# pinout_v1.net
KiCad netlist of a schematic drawn in Altium Designer
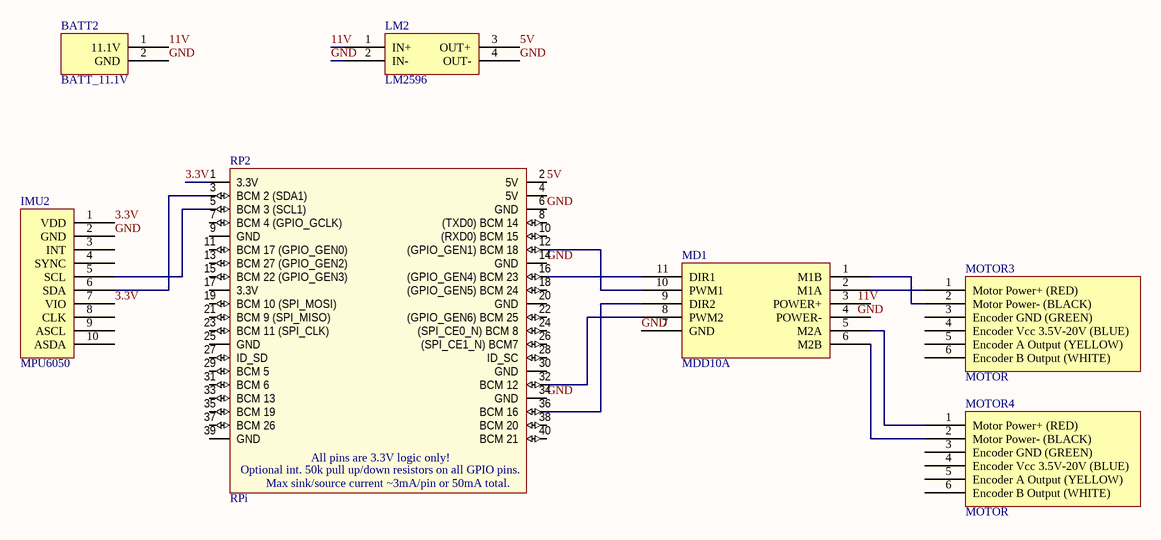
[diagram p0: pinout_v1.SchDoc]

(export (version "E")
  (design (tool "Eeschema 10.0.6"))
  (components
    (comp (ref "BATT2")
      (value "BATT_11.1V")
      (description "11.1V, 4000mAh, 40C 3S LiPo Battery")
      (libsource (lib "pinout") (part "BATT_11.1V"))
    )
    (comp (ref "IMU2")
      (value "MPU6050")
      (description "SparkFun Triple Axis Accelerometer and Gyro Breakout")
      (libsource (lib "pinout") (part "MPU6050"))
    )
    (comp (ref "LM2") (value "LM2596") (libsource (lib "pinout") (part "LM2596")))
    (comp (ref "MD1")
      (value "MDD10A")
      (description "Cytron 10A 5-30V Dual Channel DC Motor Driver")
      (libsource (lib "pinout") (part "MDD10A"))
    )
    (comp (ref "MOTOR3")
      (value "MOTOR")
      (description "30:1 Metal Gearmotor 37Dx68L mm with 64 CPR Encoder")
      (libsource (lib "pinout") (part "MOTOR"))
    )
    (comp (ref "MOTOR4")
      (value "MOTOR")
      (description "30:1 Metal Gearmotor 37Dx68L mm with 64 CPR Encoder")
      (libsource (lib "pinout") (part "MOTOR"))
    )
    (comp (ref "RP2")
      (value "RPi")
      (footprint "40-Pin IDC Connector 2.54mm Pitch")
      (description "40-pin IDC 2.54mm P Header with RPi 2+ GPIO pinout")
      (fields (field (name "MOUSER PART #") "571-3-1761603-3"))
      (libsource (lib "pinout") (part "RPi"))
    )
  )
  (nets
    (net (code "1") (name "/3.3V") (class "Default")
      (node (ref "IMU2") (pin "1") (pinfunction "VDD_1") (pintype "passive"))
      (node (ref "IMU2") (pin "7") (pinfunction "VIO_7") (pintype "passive"))
      (node (ref "RP2") (pin "1") (pinfunction "3.3V_1") (pintype "power_in"))
    )
    (net (code "2") (name "/5V") (class "Default")
      (node (ref "LM2") (pin "3") (pinfunction "OUT+_3") (pintype "passive"))
      (node (ref "RP2") (pin "2") (pinfunction "5V_2") (pintype "power_in"))
    )
    (net (code "3") (name "/11V") (class "Default")
      (node (ref "BATT2") (pin "1") (pinfunction "11.1V_1") (pintype "passive"))
      (node (ref "LM2") (pin "1") (pinfunction "IN+_1") (pintype "passive"))
      (node (ref "MD1") (pin "3") (pinfunction "POWER+_3") (pintype "passive"))
    )
    (net (code "4") (name "/GND") (class "Default")
      (node (ref "BATT2") (pin "2") (pinfunction "GND_2") (pintype "passive"))
      (node (ref "IMU2") (pin "2") (pinfunction "GND_2") (pintype "passive"))
      (node (ref "LM2") (pin "2") (pinfunction "IN-_2") (pintype "passive"))
      (node (ref "LM2") (pin "4") (pinfunction "OUT-_4") (pintype "passive"))
      (node (ref "MD1") (pin "4") (pinfunction "POWER-_4") (pintype "passive"))
      (node (ref "MD1") (pin "7") (pinfunction "GND_7") (pintype "passive"))
      (node (ref "RP2") (pin "14") (pinfunction "GND_14") (pintype "power_in"))
      (node (ref "RP2") (pin "34") (pinfunction "GND_34") (pintype "power_in"))
      (node (ref "RP2") (pin "6") (pinfunction "GND_6") (pintype "power_in"))
    )
    (net (code "5") (name "Net-(IMU2-SCL)") (class "Default")
      (node (ref "IMU2") (pin "5") (pinfunction "SCL_5") (pintype "passive"))
      (node (ref "RP2") (pin "5") (pinfunction "BCM_3_(SCL1)_5") (pintype "bidirectional"))
    )
    (net (code "6") (name "Net-(IMU2-SDA)") (class "Default")
      (node (ref "IMU2") (pin "6") (pinfunction "SDA_6") (pintype "passive"))
      (node (ref "RP2") (pin "3") (pinfunction "BCM_2_(SDA1)_3") (pintype "bidirectional"))
    )
    (net (code "7") (name "Net-(MD1-DIR1)") (class "Default")
      (node (ref "MD1") (pin "11") (pinfunction "DIR1_11") (pintype "passive"))
      (node (ref "RP2") (pin "16") (pinfunction "(GPIO_GEN4)_BCM_23_16") (pintype "bidirectional"))
    )
    (net (code "8") (name "Net-(MD1-DIR2)") (class "Default")
      (node (ref "MD1") (pin "9") (pinfunction "DIR2_9") (pintype "passive"))
      (node (ref "RP2") (pin "36") (pinfunction "BCM_16_36") (pintype "bidirectional"))
    )
    (net (code "9") (name "Net-(MD1-M1A)") (class "Default")
      (node (ref "MD1") (pin "2") (pinfunction "M1A_2") (pintype "passive"))
      (node (ref "MOTOR3") (pin "1") (pinfunction "Motor_Power+_(RED)_1") (pintype "passive"))
    )
    (net (code "10") (name "Net-(MD1-M1B)") (class "Default")
      (node (ref "MD1") (pin "1") (pinfunction "M1B_1") (pintype "passive"))
      (node (ref "MOTOR3") (pin "2") (pinfunction "Motor_Power-_(BLACK)_2") (pintype "passive"))
    )
    (net (code "11") (name "Net-(MD1-M2A)") (class "Default")
      (node (ref "MD1") (pin "5") (pinfunction "M2A_5") (pintype "passive"))
      (node (ref "MOTOR4") (pin "1") (pinfunction "Motor_Power+_(RED)_1") (pintype "passive"))
    )
    (net (code "12") (name "Net-(MD1-M2B)") (class "Default")
      (node (ref "MD1") (pin "6") (pinfunction "M2B_6") (pintype "passive"))
      (node (ref "MOTOR4") (pin "2") (pinfunction "Motor_Power-_(BLACK)_2") (pintype "passive"))
    )
    (net (code "13") (name "Net-(MD1-PWM1)") (class "Default")
      (node (ref "MD1") (pin "10") (pinfunction "PWM1_10") (pintype "passive"))
      (node (ref "RP2") (pin "12") (pinfunction "(GPIO_GEN1)_BCM_18_12") (pintype "bidirectional"))
    )
    (net (code "14") (name "Net-(MD1-PWM2)") (class "Default")
      (node (ref "MD1") (pin "8") (pinfunction "PWM2_8") (pintype "passive"))
      (node (ref "RP2") (pin "32") (pinfunction "BCM_12_32") (pintype "bidirectional"))
    )
    (net (code "15") (name "unconnected-(IMU2-ASCL-Pad9)") (class "Default")
      (node (ref "IMU2") (pin "9") (pinfunction "ASCL_9") (pintype "passive"))
    )
    (net (code "16") (name "unconnected-(IMU2-ASDA-Pad10)") (class "Default")
      (node (ref "IMU2") (pin "10") (pinfunction "ASDA_10") (pintype "passive"))
    )
    (net (code "17") (name "unconnected-(IMU2-CLK-Pad8)") (class "Default")
      (node (ref "IMU2") (pin "8") (pinfunction "CLK_8") (pintype "passive"))
    )
    (net (code "18") (name "unconnected-(IMU2-INT-Pad3)") (class "Default")
      (node (ref "IMU2") (pin "3") (pinfunction "INT_3") (pintype "passive"))
    )
    (net (code "19") (name "unconnected-(IMU2-SYNC-Pad4)") (class "Default")
      (node (ref "IMU2") (pin "4") (pinfunction "SYNC_4") (pintype "passive"))
    )
    (net (code "20") (name "unconnected-(MOTOR3-Encoder_A_Output_(YELLOW)-Pad5)") (class "Default")
      (node (ref "MOTOR3") (pin "5") (pinfunction "Encoder_A_Output_(YELLOW)_5") (pintype "passive"))
    )
    (net (code "21") (name "unconnected-(MOTOR3-Encoder_B_Output_(WHITE)-Pad6)") (class "Default")
      (node (ref "MOTOR3") (pin "6") (pinfunction "Encoder_B_Output_(WHITE)_6") (pintype "passive"))
    )
    (net (code "22") (name "unconnected-(MOTOR3-Encoder_GND_(GREEN)-Pad3)") (class "Default")
      (node (ref "MOTOR3") (pin "3") (pinfunction "Encoder_GND_(GREEN)_3") (pintype "passive"))
    )
    (net (code "23") (name "unconnected-(MOTOR3-Encoder_Vcc_3.5V-20V_(BLUE)-Pad4)") (class "Default")
      (node (ref "MOTOR3") (pin "4") (pinfunction "Encoder_Vcc_3.5V-20V_(BLUE)_4") (pintype "passive"))
    )
    (net (code "24") (name "unconnected-(MOTOR4-Encoder_A_Output_(YELLOW)-Pad5)") (class "Default")
      (node (ref "MOTOR4") (pin "5") (pinfunction "Encoder_A_Output_(YELLOW)_5") (pintype "passive"))
    )
    (net (code "25") (name "unconnected-(MOTOR4-Encoder_B_Output_(WHITE)-Pad6)") (class "Default")
      (node (ref "MOTOR4") (pin "6") (pinfunction "Encoder_B_Output_(WHITE)_6") (pintype "passive"))
    )
    (net (code "26") (name "unconnected-(MOTOR4-Encoder_GND_(GREEN)-Pad3)") (class "Default")
      (node (ref "MOTOR4") (pin "3") (pinfunction "Encoder_GND_(GREEN)_3") (pintype "passive"))
    )
    (net (code "27") (name "unconnected-(MOTOR4-Encoder_Vcc_3.5V-20V_(BLUE)-Pad4)") (class "Default")
      (node (ref "MOTOR4") (pin "4") (pinfunction "Encoder_Vcc_3.5V-20V_(BLUE)_4") (pintype "passive"))
    )
    (net (code "28") (name "unconnected-(RP2-(GPIO_GEN5)_BCM_24-Pad18)") (class "Default")
      (node (ref "RP2") (pin "18") (pinfunction "(GPIO_GEN5)_BCM_24_18") (pintype "bidirectional"))
    )
    (net (code "29") (name "unconnected-(RP2-(GPIO_GEN6)_BCM_25-Pad22)") (class "Default")
      (node (ref "RP2") (pin "22") (pinfunction "(GPIO_GEN6)_BCM_25_22") (pintype "bidirectional"))
    )
    (net (code "30") (name "unconnected-(RP2-(RXD0)_BCM_15-Pad10)") (class "Default")
      (node (ref "RP2") (pin "10") (pinfunction "(RXD0)_BCM_15_10") (pintype "bidirectional"))
    )
    (net (code "31") (name "unconnected-(RP2-(SPI_CE0_N)_BCM_8-Pad24)") (class "Default")
      (node (ref "RP2") (pin "24") (pinfunction "(SPI_CE0_N)_BCM_8_24") (pintype "bidirectional"))
    )
    (net (code "32") (name "unconnected-(RP2-(SPI_CE1_N)_BCM7-Pad26)") (class "Default")
      (node (ref "RP2") (pin "26") (pinfunction "(SPI_CE1_N)_BCM7_26") (pintype "bidirectional"))
    )
    (net (code "33") (name "unconnected-(RP2-(TXD0)_BCM_14-Pad8)") (class "Default")
      (node (ref "RP2") (pin "8") (pinfunction "(TXD0)_BCM_14_8") (pintype "bidirectional"))
    )
    (net (code "34") (name "unconnected-(RP2-3.3V-Pad17)") (class "Default")
      (node (ref "RP2") (pin "17") (pinfunction "3.3V_17") (pintype "power_in"))
    )
    (net (code "35") (name "unconnected-(RP2-5V-Pad4)") (class "Default")
      (node (ref "RP2") (pin "4") (pinfunction "5V_4") (pintype "power_in"))
    )
    (net (code "36") (name "unconnected-(RP2-BCM_4_(GPIO_GCLK)-Pad7)") (class "Default")
      (node (ref "RP2") (pin "7") (pinfunction "BCM_4_(GPIO_GCLK)_7") (pintype "bidirectional"))
    )
    (net (code "37") (name "unconnected-(RP2-BCM_5-Pad29)") (class "Default")
      (node (ref "RP2") (pin "29") (pinfunction "BCM_5_29") (pintype "bidirectional"))
    )
    (net (code "38") (name "unconnected-(RP2-BCM_6-Pad31)") (class "Default")
      (node (ref "RP2") (pin "31") (pinfunction "BCM_6_31") (pintype "bidirectional"))
    )
    (net (code "39") (name "unconnected-(RP2-BCM_9_(SPI_MISO)-Pad21)") (class "Default")
      (node (ref "RP2") (pin "21") (pinfunction "BCM_9_(SPI_MISO)_21") (pintype "bidirectional"))
    )
    (net (code "40") (name "unconnected-(RP2-BCM_10_(SPI_MOSI)-Pad19)") (class "Default")
      (node (ref "RP2") (pin "19") (pinfunction "BCM_10_(SPI_MOSI)_19") (pintype "bidirectional"))
    )
    (net (code "41") (name "unconnected-(RP2-BCM_11_(SPI_CLK)-Pad23)") (class "Default")
      (node (ref "RP2") (pin "23") (pinfunction "BCM_11_(SPI_CLK)_23") (pintype "bidirectional"))
    )
    (net (code "42") (name "unconnected-(RP2-BCM_13-Pad33)") (class "Default")
      (node (ref "RP2") (pin "33") (pinfunction "BCM_13_33") (pintype "bidirectional"))
    )
    (net (code "43") (name "unconnected-(RP2-BCM_17_(GPIO_GEN0)-Pad11)") (class "Default")
      (node (ref "RP2") (pin "11") (pinfunction "BCM_17_(GPIO_GEN0)_11") (pintype "bidirectional"))
    )
    (net (code "44") (name "unconnected-(RP2-BCM_19-Pad35)") (class "Default")
      (node (ref "RP2") (pin "35") (pinfunction "BCM_19_35") (pintype "bidirectional"))
    )
    (net (code "45") (name "unconnected-(RP2-BCM_20-Pad38)") (class "Default")
      (node (ref "RP2") (pin "38") (pinfunction "BCM_20_38") (pintype "bidirectional"))
    )
    (net (code "46") (name "unconnected-(RP2-BCM_21-Pad40)") (class "Default")
      (node (ref "RP2") (pin "40") (pinfunction "BCM_21_40") (pintype "bidirectional"))
    )
    (net (code "47") (name "unconnected-(RP2-BCM_22_(GPIO_GEN3)-Pad15)") (class "Default")
      (node (ref "RP2") (pin "15") (pinfunction "BCM_22_(GPIO_GEN3)_15") (pintype "bidirectional"))
    )
    (net (code "48") (name "unconnected-(RP2-BCM_26-Pad37)") (class "Default")
      (node (ref "RP2") (pin "37") (pinfunction "BCM_26_37") (pintype "bidirectional"))
    )
    (net (code "49") (name "unconnected-(RP2-BCM_27_(GPIO_GEN2)-Pad13)") (class "Default")
      (node (ref "RP2") (pin "13") (pinfunction "BCM_27_(GPIO_GEN2)_13") (pintype "bidirectional"))
    )
    (net (code "50") (name "unconnected-(RP2-GND-Pad9)") (class "Default")
      (node (ref "RP2") (pin "9") (pinfunction "GND_9") (pintype "power_in"))
    )
    (net (code "51") (name "unconnected-(RP2-GND-Pad20)") (class "Default")
      (node (ref "RP2") (pin "20") (pinfunction "GND_20") (pintype "power_in"))
    )
    (net (code "52") (name "unconnected-(RP2-GND-Pad25)") (class "Default")
      (node (ref "RP2") (pin "25") (pinfunction "GND_25") (pintype "power_in"))
    )
    (net (code "53") (name "unconnected-(RP2-GND-Pad30)") (class "Default")
      (node (ref "RP2") (pin "30") (pinfunction "GND_30") (pintype "power_in"))
    )
    (net (code "54") (name "unconnected-(RP2-GND-Pad39)") (class "Default")
      (node (ref "RP2") (pin "39") (pinfunction "GND_39") (pintype "power_in"))
    )
    (net (code "55") (name "unconnected-(RP2-ID_SC-Pad28)") (class "Default")
      (node (ref "RP2") (pin "28") (pinfunction "ID_SC_28") (pintype "bidirectional"))
    )
    (net (code "56") (name "unconnected-(RP2-ID_SD-Pad27)") (class "Default")
      (node (ref "RP2") (pin "27") (pinfunction "ID_SD_27") (pintype "bidirectional"))
    )
  )
)
